# Thermistor.net
KiCad netlist of a schematic drawn in Altium Designer
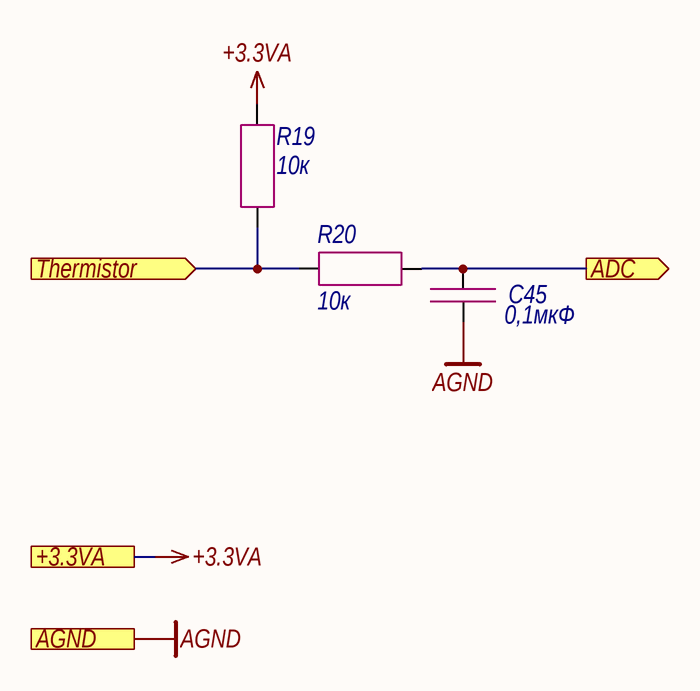
[diagram p0: Thermistor.SchDoc]

(export (version "E")
  (design (tool "Eeschema 10.0.6"))
  (components
    (comp (ref "C45")
      (value "0,1мкФ")
      (footprint "Pcb_library:CAP_0603")
      (fields (field (name "MANUFACTURER") "Murata"))
      (libsource (lib "Schem_library") (part "Capacitor"))
    )
    (comp (ref "R19")
      (value "10к")
      (footprint "Pcb_library:RES_0603")
      (fields (field (name "MANUFACTURER") "Yageo"))
      (libsource (lib "Schem_library") (part "Resistor"))
    )
    (comp (ref "R20")
      (value "10к")
      (footprint "Pcb_library:RES_0603")
      (fields (field (name "MANUFACTURER") "Yageo"))
      (libsource (lib "Schem_library") (part "Resistor"))
    )
  )
  (nets
    (net (code "1") (name "+3.3VA") (class "Default")
      (node (ref "R19") (pin "1") (pinfunction "1_1") (pintype "passive"))
    )
    (net (code "2") (name "/ADC") (class "Default")
      (node (ref "C45") (pin "1") (pinfunction "1_1") (pintype "passive"))
      (node (ref "R20") (pin "2") (pinfunction "2_2") (pintype "passive"))
    )
    (net (code "3") (name "/Thermistor") (class "Default")
      (node (ref "R19") (pin "2") (pinfunction "2_2") (pintype "passive"))
      (node (ref "R20") (pin "1") (pinfunction "1_1") (pintype "passive"))
    )
    (net (code "4") (name "AGND") (class "Default")
      (node (ref "C45") (pin "2") (pinfunction "2_2") (pintype "passive"))
    )
  )
)
